# CD4060BM_CD4908.net
KiCad netlist of a schematic drawn in Altium Designer
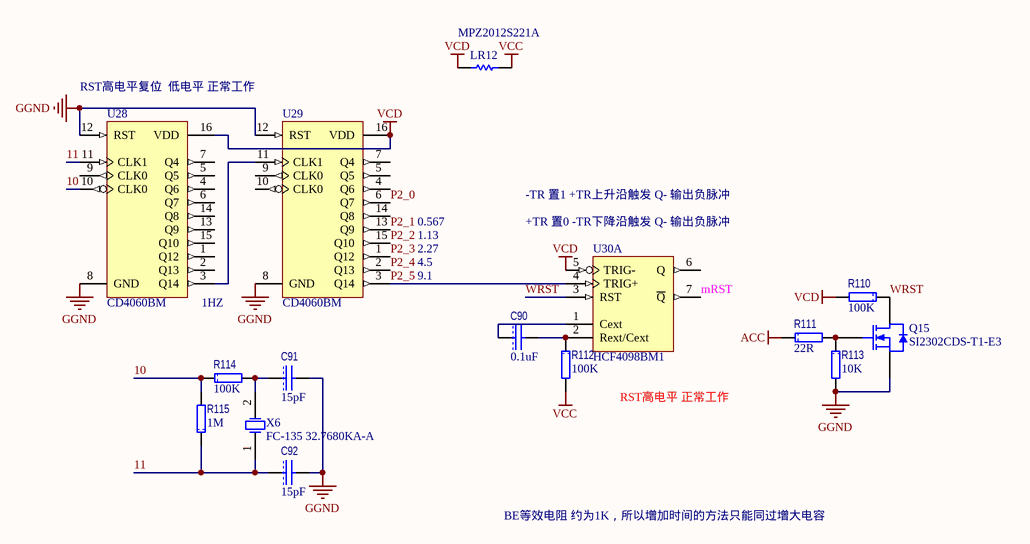
[diagram p0: CD4060BM+CD4908_硬件定时器.SchDoc]

(export (version "E")
  (design (tool "Eeschema 10.0.6"))
  (components
    (comp (ref "C90")
      (value "0.1uF")
      (footprint "1608[0603]C")
      (description "多层陶瓷电容器MLCC - SMD/SMT 0603 0.1uF 50volts X7R 10%")
      (fields (field (name "MANUFACTURER") "TDK") (field (name "MANUFACTURER PART NUMBER") "C1608X7R1H104K"))
      (libsource (lib "*") (part "CAP"))
    )
    (comp (ref "C91")
      (value "15pF")
      (footprint "1608[0603]C")
      (description "多层陶瓷电容器MLCC - SMD/SMT 0603 15pF 50volts C0G 5%")
      (fields (field (name "MANUFACTURER") "TDK") (field (name "MANUFACTURER PART NUMBER") "C1608C0G1H150J"))
      (libsource (lib "*") (part "CAP"))
    )
    (comp (ref "C92")
      (value "15pF")
      (footprint "1608[0603]C")
      (description "多层陶瓷电容器MLCC - SMD/SMT 0603 15pF 50volts C0G 5%")
      (fields (field (name "MANUFACTURER") "TDK") (field (name "MANUFACTURER PART NUMBER") "C1608C0G1H150J"))
      (libsource (lib "*") (part "CAP"))
    )
    (comp (ref "LR12")
      (value "MPZ2012S221A")
      (footprint "2012[0805]")
      (description "电磁干扰滤波珠子、扼流圈和阵列 Ferrite Chip Beads")
      (fields (field (name "MANUFACTURER") "TDK"))
      (libsource (lib "Miscellaneous Devices") (part "Res Semi"))
    )
    (comp (ref "Q15")
      (value "SI2302CDS-T1-E3")
      (footprint "SOT23_N")
      (description "MOSFET 20V 2.9A 0.86W 57mohm @ 4.5V")
      (fields (field (name "MANUFACTURER") "Vishay / Siliconix"))
      (libsource (lib "Philips Discrete MOSFET - Low Power") (part "2N7002"))
    )
    (comp (ref "R110")
      (value "100K")
      (footprint "1608[0603]R")
      (description "厚膜电阻器 - SMD 1/10watt 100Kohms 1%")
      (fields
        (field (name "MANUFACTURER") "Vishay / Dale")
        (field (name "MANUFACTURER PART NUMBER") "CRCW0603100KFKEA")
      )
      (libsource (lib "100K 1%") (part "RES"))
    )
    (comp (ref "R111")
      (value "22R")
      (footprint "1608[0603]R")
      (description "厚膜电阻器 - SMD 1/10watt 22ohms 1%")
      (fields
        (field (name "MANUFACTURER") "Vishay / Dale")
        (field (name "MANUFACTURER PART NUMBER") "CRCW060322R0FKEA")
      )
      (libsource (lib "22R 1%") (part "RES"))
    )
    (comp (ref "R112")
      (value "100K")
      (footprint "1608[0603]R")
      (description "厚膜电阻器 - SMD 1/10watt 100Kohms 1%")
      (fields
        (field (name "MANUFACTURER") "Vishay / Dale")
        (field (name "MANUFACTURER PART NUMBER") "CRCW0603100KFKEA")
      )
      (libsource (lib "100K 1%") (part "RES"))
    )
    (comp (ref "R113")
      (value "10K")
      (footprint "1608[0603]R")
      (description "厚膜电阻器 - SMD 1/10watt 10Kohms 1%")
      (fields
        (field (name "MANUFACTURER") "Vishay / Dale")
        (field (name "MANUFACTURER PART NUMBER") "CRCW060310K0FKEA")
      )
      (libsource (lib "10K 1%") (part "RES"))
    )
    (comp (ref "R114")
      (value "100K")
      (footprint "1608[0603]R")
      (description "厚膜电阻器 - SMD 1/10watt 100Kohms 1%")
      (fields
        (field (name "MANUFACTURER") "Vishay / Dale")
        (field (name "MANUFACTURER PART NUMBER") "CRCW0603100KFKEA")
      )
      (libsource (lib "100K 1%") (part "RES"))
    )
    (comp (ref "R115")
      (value "1M")
      (footprint "1608[0603]R")
      (description "厚膜电阻器 - SMD 1/10watt 1.0Mohms 1%")
      (fields
        (field (name "MANUFACTURER") "Vishay / Dale")
        (field (name "MANUFACTURER PART NUMBER") "CRCW06031M00FKEA")
      )
      (libsource (lib "1M 1%") (part "RES"))
    )
    (comp (ref "U28")
      (value "CD4060BM")
      (footprint "SOIC16_N")
      (description "14-Stage Ripple Carry Binary Counter")
      (fields (field (name "PUBLISHER") "Altium Limited"))
      (libsource (lib "FSC Logic Counter") (part "CD4060BCM"))
    )
    (comp (ref "U29")
      (value "CD4060BM")
      (footprint "SOIC16_N")
      (description "14-Stage Ripple Carry Binary Counter")
      (fields (field (name "PUBLISHER") "Altium Limited"))
      (libsource (lib "FSC Logic Counter") (part "CD4060BCM"))
    )
    (comp (ref "U30")
      (value "HCF4098BM1")
      (footprint "SO16_N")
      (description "Dual Monostable Multivibrator")
      (fields (field (name "PUBLISHER") "Altium Limited"))
      (libsource (lib "ST Logic Multivibrator") (part "HCF4098BM1"))
    )
    (comp (ref "X6")
      (value "FC-135 32.7680KA-A")
      (footprint "FC-135")
      (description "晶体 32.768KHz 20ppm 12.5pF -40C -85C")
      (fields (field (name "MANUFACTURER") "Epson Toyocom"))
      (libsource (lib "Miscellaneous Devices") (part "XTAL"))
    )
  )
  (nets
    (net (code "1") (name "/10") (class "Default")
      (node (ref "R114") (pin "1") (pinfunction "1_1") (pintype "passive"))
      (node (ref "R115") (pin "2") (pinfunction "2_2") (pintype "passive"))
      (node (ref "U28") (pin "10") (pinfunction "CLK0_10") (pintype "output"))
    )
    (net (code "2") (name "/11") (class "Default")
      (node (ref "C92") (pin "1") (pinfunction "1_1") (pintype "passive"))
      (node (ref "R115") (pin "1") (pinfunction "1_1") (pintype "passive"))
      (node (ref "U28") (pin "11") (pinfunction "CLK1_11") (pintype "input"))
      (node (ref "X6") (pin "1") (pinfunction "OSC1_1") (pintype "passive"))
    )
    (net (code "3") (name "/P2_0") (class "Default")
      (node (ref "U29") (pin "6") (pinfunction "Q7_6") (pintype "output"))
    )
    (net (code "4") (name "/P2_1") (class "Default")
      (node (ref "U29") (pin "13") (pinfunction "Q9_13") (pintype "output"))
    )
    (net (code "5") (name "/P2_2") (class "Default")
      (node (ref "U29") (pin "15") (pinfunction "Q10_15") (pintype "output"))
    )
    (net (code "6") (name "/P2_3") (class "Default")
      (node (ref "U29") (pin "1") (pinfunction "Q12_1") (pintype "output"))
    )
    (net (code "7") (name "/P2_4") (class "Default")
      (node (ref "U29") (pin "2") (pinfunction "Q13_2") (pintype "output"))
    )
    (net (code "8") (name "/P2_5") (class "Default")
      (node (ref "U29") (pin "3") (pinfunction "Q14_3") (pintype "output"))
      (node (ref "U30") (pin "4") (pinfunction "TRIG+_4") (pintype "input"))
    )
    (net (code "9") (name "/WRST") (class "Default")
      (node (ref "Q15") (pin "3") (pinfunction "D_3") (pintype "passive"))
      (node (ref "R110") (pin "1") (pinfunction "1_1") (pintype "passive"))
      (node (ref "U30") (pin "3") (pinfunction "RST_3") (pintype "input"))
    )
    (net (code "10") (name "/mRST") (class "Default")
      (node (ref "U30") (pin "7") (pinfunction "~{Q}_7") (pintype "output"))
    )
    (net (code "11") (name "ACC") (class "Default")
      (node (ref "R111") (pin "1") (pinfunction "1_1") (pintype "passive"))
    )
    (net (code "12") (name "GGND") (class "Default")
      (node (ref "C91") (pin "2") (pinfunction "2_2") (pintype "passive"))
      (node (ref "C92") (pin "2") (pinfunction "2_2") (pintype "passive"))
      (node (ref "Q15") (pin "2") (pinfunction "S_2") (pintype "passive"))
      (node (ref "R113") (pin "2") (pinfunction "2_2") (pintype "passive"))
      (node (ref "U28") (pin "12") (pinfunction "RST_12") (pintype "input"))
      (node (ref "U28") (pin "8") (pinfunction "GND_8") (pintype "power_in"))
      (node (ref "U29") (pin "12") (pinfunction "RST_12") (pintype "input"))
      (node (ref "U29") (pin "8") (pinfunction "GND_8") (pintype "power_in"))
    )
    (net (code "13") (name "GND") (class "Default")
      (node (ref "U30") (pin "8") (pinfunction "GND_8") (pintype "power_in"))
    )
    (net (code "14") (name "Net-(Q15-G)") (class "Default")
      (node (ref "Q15") (pin "1") (pinfunction "G_1") (pintype "passive"))
      (node (ref "R111") (pin "2") (pinfunction "2_2") (pintype "passive"))
      (node (ref "R113") (pin "1") (pinfunction "1_1") (pintype "passive"))
    )
    (net (code "15") (name "Net-(U28-Q14)") (class "Default")
      (node (ref "U28") (pin "3") (pinfunction "Q14_3") (pintype "output"))
      (node (ref "U29") (pin "11") (pinfunction "CLK1_11") (pintype "input"))
    )
    (net (code "16") (name "Net-(U30A-Cext)") (class "Default")
      (node (ref "C90") (pin "1") (pinfunction "1_1") (pintype "passive"))
      (node (ref "U30") (pin "1") (pinfunction "Cext_1") (pintype "passive"))
    )
    (net (code "17") (name "Net-(U30A-Rext{slash}Cext)") (class "Default")
      (node (ref "C90") (pin "2") (pinfunction "2_2") (pintype "passive"))
      (node (ref "R112") (pin "1") (pinfunction "1_1") (pintype "passive"))
      (node (ref "U30") (pin "2") (pinfunction "Rext/Cext_2") (pintype "passive"))
    )
    (net (code "18") (name "Net-(X6-OSC2)") (class "Default")
      (node (ref "C91") (pin "1") (pinfunction "1_1") (pintype "passive"))
      (node (ref "R114") (pin "2") (pinfunction "2_2") (pintype "passive"))
      (node (ref "X6") (pin "2") (pinfunction "OSC2_2") (pintype "passive"))
    )
    (net (code "19") (name "VCC") (class "Default")
      (node (ref "LR12") (pin "1") (pinfunction "1_1") (pintype "passive"))
      (node (ref "R112") (pin "2") (pinfunction "2_2") (pintype "passive"))
      (node (ref "U30") (pin "16") (pinfunction "VCC_16") (pintype "power_in"))
    )
    (net (code "20") (name "VCD") (class "Default")
      (node (ref "LR12") (pin "2") (pinfunction "2_2") (pintype "passive"))
      (node (ref "R110") (pin "2") (pinfunction "2_2") (pintype "passive"))
      (node (ref "U28") (pin "16") (pinfunction "VDD_16") (pintype "power_in"))
      (node (ref "U29") (pin "16") (pinfunction "VDD_16") (pintype "power_in"))
      (node (ref "U30") (pin "5") (pinfunction "TRIG-_5") (pintype "input"))
    )
    (net (code "21") (name "unconnected-(U28-CLK0-Pad9)") (class "Default")
      (node (ref "U28") (pin "9") (pinfunction "CLK0_9") (pintype "output"))
    )
    (net (code "22") (name "unconnected-(U28-Q4-Pad7)") (class "Default")
      (node (ref "U28") (pin "7") (pinfunction "Q4_7") (pintype "output"))
    )
    (net (code "23") (name "unconnected-(U28-Q5-Pad5)") (class "Default")
      (node (ref "U28") (pin "5") (pinfunction "Q5_5") (pintype "output"))
    )
    (net (code "24") (name "unconnected-(U28-Q6-Pad4)") (class "Default")
      (node (ref "U28") (pin "4") (pinfunction "Q6_4") (pintype "output"))
    )
    (net (code "25") (name "unconnected-(U28-Q7-Pad6)") (class "Default")
      (node (ref "U28") (pin "6") (pinfunction "Q7_6") (pintype "output"))
    )
    (net (code "26") (name "unconnected-(U28-Q8-Pad14)") (class "Default")
      (node (ref "U28") (pin "14") (pinfunction "Q8_14") (pintype "output"))
    )
    (net (code "27") (name "unconnected-(U28-Q9-Pad13)") (class "Default")
      (node (ref "U28") (pin "13") (pinfunction "Q9_13") (pintype "output"))
    )
    (net (code "28") (name "unconnected-(U28-Q10-Pad15)") (class "Default")
      (node (ref "U28") (pin "15") (pinfunction "Q10_15") (pintype "output"))
    )
    (net (code "29") (name "unconnected-(U28-Q12-Pad1)") (class "Default")
      (node (ref "U28") (pin "1") (pinfunction "Q12_1") (pintype "output"))
    )
    (net (code "30") (name "unconnected-(U28-Q13-Pad2)") (class "Default")
      (node (ref "U28") (pin "2") (pinfunction "Q13_2") (pintype "output"))
    )
    (net (code "31") (name "unconnected-(U29-CLK0-Pad9)") (class "Default")
      (node (ref "U29") (pin "9") (pinfunction "CLK0_9") (pintype "output"))
    )
    (net (code "32") (name "unconnected-(U29-CLK0-Pad10)") (class "Default")
      (node (ref "U29") (pin "10") (pinfunction "CLK0_10") (pintype "output"))
    )
    (net (code "33") (name "unconnected-(U29-Q4-Pad7)") (class "Default")
      (node (ref "U29") (pin "7") (pinfunction "Q4_7") (pintype "output"))
    )
    (net (code "34") (name "unconnected-(U29-Q5-Pad5)") (class "Default")
      (node (ref "U29") (pin "5") (pinfunction "Q5_5") (pintype "output"))
    )
    (net (code "35") (name "unconnected-(U29-Q6-Pad4)") (class "Default")
      (node (ref "U29") (pin "4") (pinfunction "Q6_4") (pintype "output"))
    )
    (net (code "36") (name "unconnected-(U29-Q8-Pad14)") (class "Default")
      (node (ref "U29") (pin "14") (pinfunction "Q8_14") (pintype "output"))
    )
    (net (code "37") (name "unconnected-(U30A-Q-Pad6)") (class "Default")
      (node (ref "U30") (pin "6") (pinfunction "Q_6") (pintype "output"))
    )
  )
)
